# can_comparators.net
KiCad netlist of a schematic drawn in Altium Designer
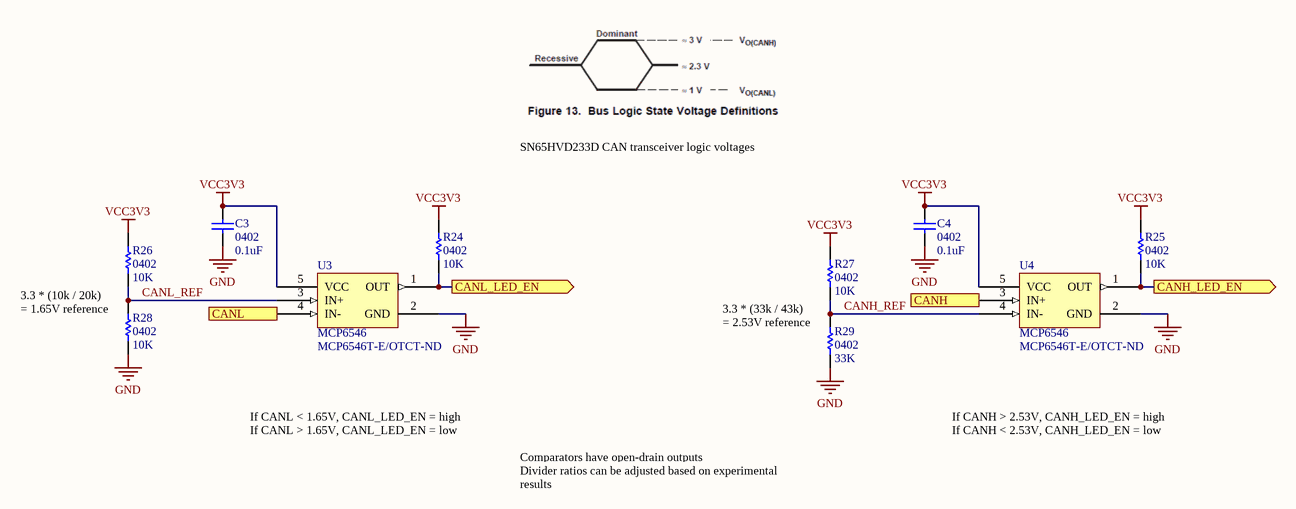
[diagram p0: can_comparators.SchDoc]

(export (version "E")
  (design (tool "Eeschema 10.0.6"))
  (components
    (comp (ref "C3")
      (value "0402")
      (footprint "CAP0402R")
      (description "0402 capacitor")
      (fields (field (name "ALTIUM_VALUE") "0.1uF"))
      (libsource (lib "heron-general") (part "CAP0402"))
    )
    (comp (ref "C4")
      (value "0402")
      (footprint "CAP0402R")
      (description "0402 capacitor")
      (fields (field (name "ALTIUM_VALUE") "0.1uF"))
      (libsource (lib "heron-general") (part "CAP0402"))
    )
    (comp (ref "R24")
      (value "0402")
      (footprint "RES0402R")
      (description "0402 resistor")
      (fields (field (name "ALTIUM_VALUE") "10K"))
      (libsource (lib "heron-general") (part "RES0402"))
    )
    (comp (ref "R25")
      (value "0402")
      (footprint "RES0402R")
      (description "0402 resistor")
      (fields (field (name "ALTIUM_VALUE") "10K"))
      (libsource (lib "heron-general") (part "RES0402"))
    )
    (comp (ref "R26")
      (value "0402")
      (footprint "RES0402R")
      (description "0402 resistor")
      (fields (field (name "ALTIUM_VALUE") "10K"))
      (libsource (lib "heron-general") (part "RES0402"))
    )
    (comp (ref "R27")
      (value "0402")
      (footprint "RES0402R")
      (description "0402 resistor")
      (fields (field (name "ALTIUM_VALUE") "10K"))
      (libsource (lib "heron-general") (part "RES0402"))
    )
    (comp (ref "R28")
      (value "0402")
      (footprint "RES0402R")
      (description "0402 resistor")
      (fields (field (name "ALTIUM_VALUE") "10K"))
      (libsource (lib "heron-general") (part "RES0402"))
    )
    (comp (ref "R29")
      (value "0402")
      (footprint "RES0402R")
      (description "0402 resistor")
      (fields (field (name "ALTIUM_VALUE") "33K"))
      (libsource (lib "heron-general") (part "RES0402"))
    )
    (comp (ref "U3")
      (value "MCP6546")
      (footprint "SOT95P290X160-5N")
      (description "Open-drain output sub-microamp comparator.")
      (fields (field (name "SUPPLIER PART NUMBER 1") "MCP6546T-E/OTCT-ND"))
      (libsource (lib "heron-general") (part "MCP6546"))
    )
    (comp (ref "U4")
      (value "MCP6546")
      (footprint "SOT95P290X160-5N")
      (description "Open-drain output sub-microamp comparator.")
      (fields (field (name "SUPPLIER PART NUMBER 1") "MCP6546T-E/OTCT-ND"))
      (libsource (lib "heron-general") (part "MCP6546"))
    )
  )
  (nets
    (net (code "1") (name "/CANH") (class "Default")
      (node (ref "U4") (pin "3") (pinfunction "IN+_3") (pintype "input"))
    )
    (net (code "2") (name "/CANH_LED_EN") (class "Default")
      (node (ref "R25") (pin "1") (pinfunction "1_1") (pintype "passive"))
      (node (ref "U4") (pin "1") (pinfunction "OUT_1") (pintype "output"))
    )
    (net (code "3") (name "/CANH_REF") (class "Default")
      (node (ref "R27") (pin "1") (pinfunction "1_1") (pintype "passive"))
      (node (ref "R29") (pin "2") (pinfunction "2_2") (pintype "passive"))
      (node (ref "U4") (pin "4") (pinfunction "IN-_4") (pintype "input"))
    )
    (net (code "4") (name "/CANL") (class "Default")
      (node (ref "U3") (pin "4") (pinfunction "IN-_4") (pintype "input"))
    )
    (net (code "5") (name "/CANL_LED_EN") (class "Default")
      (node (ref "R24") (pin "1") (pinfunction "1_1") (pintype "passive"))
      (node (ref "U3") (pin "1") (pinfunction "OUT_1") (pintype "output"))
    )
    (net (code "6") (name "/CANL_REF") (class "Default")
      (node (ref "R26") (pin "1") (pinfunction "1_1") (pintype "passive"))
      (node (ref "R28") (pin "2") (pinfunction "2_2") (pintype "passive"))
      (node (ref "U3") (pin "3") (pinfunction "IN+_3") (pintype "input"))
    )
    (net (code "7") (name "GND") (class "Default")
      (node (ref "C3") (pin "1") (pinfunction "1_1") (pintype "passive"))
      (node (ref "C4") (pin "1") (pinfunction "1_1") (pintype "passive"))
      (node (ref "R28") (pin "1") (pinfunction "1_1") (pintype "passive"))
      (node (ref "R29") (pin "1") (pinfunction "1_1") (pintype "passive"))
      (node (ref "U3") (pin "2") (pinfunction "GND_2") (pintype "power_in"))
      (node (ref "U4") (pin "2") (pinfunction "GND_2") (pintype "power_in"))
    )
    (net (code "8") (name "VCC3V3") (class "Default")
      (node (ref "C3") (pin "2") (pinfunction "2_2") (pintype "passive"))
      (node (ref "C4") (pin "2") (pinfunction "2_2") (pintype "passive"))
      (node (ref "R24") (pin "2") (pinfunction "2_2") (pintype "passive"))
      (node (ref "R25") (pin "2") (pinfunction "2_2") (pintype "passive"))
      (node (ref "R26") (pin "2") (pinfunction "2_2") (pintype "passive"))
      (node (ref "R27") (pin "2") (pinfunction "2_2") (pintype "passive"))
      (node (ref "U3") (pin "5") (pinfunction "VCC_5") (pintype "power_in"))
      (node (ref "U4") (pin "5") (pinfunction "VCC_5") (pintype "power_in"))
    )
  )
)
